# first-alert-shield.net
KiCad netlist of a schematic drawn in EAGLE
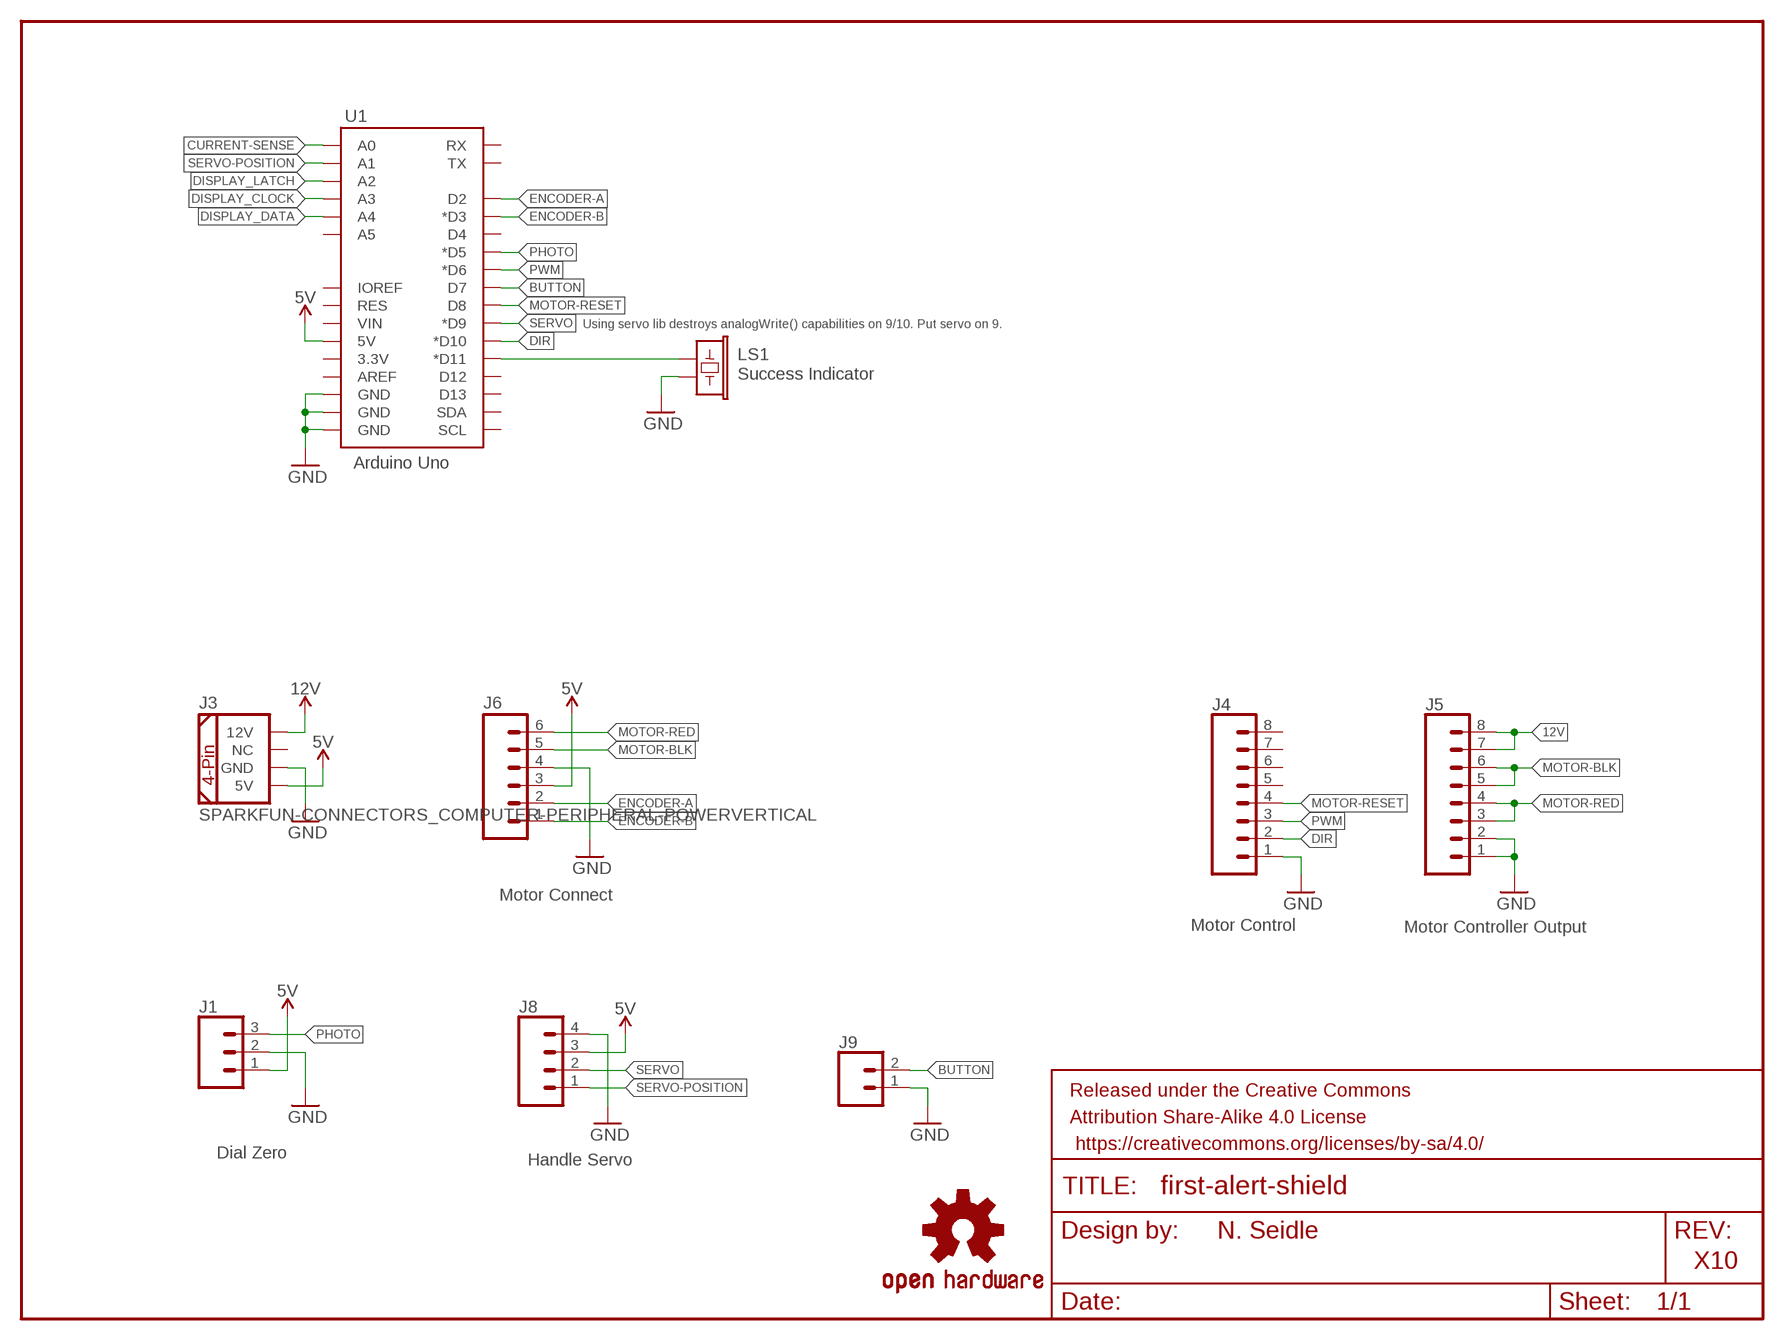
[diagram p0: schematic, sheet 1]

(export (version "E")
  (design (tool "Eeschema 10.0.6"))
  (components
    (comp (ref "FRAME1")
      (value "FRAME-LETTER")
      (footprint "eagle-import:CREATIVE_COMMONS")
      (libsource (lib "eagle-import") (part "FRAME-LETTER"))
    )
    (comp (ref "J1")
      (value "CONN_03JST-PTH-VERT")
      (footprint "eagle-import:JST-3-PTH-VERT")
      (libsource (lib "eagle-import") (part "CONN_03JST-PTH-VERT"))
    )
    (comp (ref "J3")
      (value "SPARKFUN-CONNECTORS_COMPUTER-PERIPHERAL-POWERVERTICAL")
      (footprint "eagle-import:SPARKFUN-CONNECTORS_COMPUTER-PERIPHERAL-POWER")
      (libsource (lib "eagle-import") (part "SPARKFUN-CONNECTORS_COMPUTER-PERIPHERAL-POWERVERTICAL"))
    )
    (comp (ref "J4")
      (value "Motor Control")
      (footprint "eagle-import:1X08")
      (libsource (lib "eagle-import") (part "CONN_08{dblquote}"))
    )
    (comp (ref "J5")
      (value "Motor Controller Output")
      (footprint "eagle-import:1X08")
      (libsource (lib "eagle-import") (part "CONN_08{dblquote}"))
    )
    (comp (ref "J6")
      (value "Motor Connect")
      (footprint "eagle-import:1X06@1")
      (libsource (lib "eagle-import") (part "M06SILK_FEMALE_PTH"))
    )
    (comp (ref "J8")
      (value "Handle Servo")
      (footprint "eagle-import:1X04")
      (libsource (lib "eagle-import") (part "CONN_04"))
    )
    (comp (ref "J9")
      (value "CONN_02JST-PTH-VERT")
      (footprint "eagle-import:JST-2-PTH-VERT")
      (libsource (lib "eagle-import") (part "CONN_02JST-PTH-VERT"))
    )
    (comp (ref "LOGO2")
      (value "OSHW-LOGOS")
      (footprint "eagle-import:OSHW-LOGO-S")
      (libsource (lib "eagle-import") (part "OSHW-LOGOS"))
    )
    (comp (ref "LS1")
      (value "Success Indicator")
      (footprint "eagle-import:BUZZER-12MM")
      (libsource (lib "eagle-import") (part "BUZZER-PTH"))
    )
    (comp (ref "U1")
      (value "Arduino Uno")
      (footprint "eagle-import:UNO_R3_SHIELD_NOLABELS")
      (libsource (lib "eagle-import") (part "ARDUINO_R3_SHIELDNOLABELS"))
    )
  )
  (nets
    (net (code "1") (name "5V") (class "Default")
      (node (ref "J1") (pin "1") (pinfunction "1_1") (pintype "passive"))
      (node (ref "J3") (pin "5V") (pinfunction "5V_5V") (pintype "passive"))
      (node (ref "J6") (pin "3") (pinfunction "3_3") (pintype "passive"))
      (node (ref "J8") (pin "3") (pinfunction "3_3") (pintype "passive"))
      (node (ref "U1") (pin "5V") (pinfunction "5V_5V") (pintype "bidirectional"))
    )
    (net (code "2") (name "12V") (class "Default")
      (node (ref "J3") (pin "12V") (pinfunction "12V_12V") (pintype "passive"))
      (node (ref "J5") (pin "7") (pinfunction "7_7") (pintype "passive"))
      (node (ref "J5") (pin "8") (pinfunction "8_8") (pintype "passive"))
    )
    (net (code "3") (name "BUTTON") (class "Default")
      (node (ref "J9") (pin "2") (pinfunction "2_2") (pintype "passive"))
      (node (ref "U1") (pin "D7") (pinfunction "D7_D7") (pintype "bidirectional"))
    )
    (net (code "4") (name "CURRENT-SENSE") (class "Default")
      (node (ref "U1") (pin "A0") (pinfunction "A0_A0") (pintype "bidirectional"))
    )
    (net (code "5") (name "DIR") (class "Default")
      (node (ref "J4") (pin "2") (pinfunction "2_2") (pintype "passive"))
      (node (ref "U1") (pin "D10") (pinfunction "*D10_D10") (pintype "bidirectional"))
    )
    (net (code "6") (name "DISPLAY_CLOCK") (class "Default")
      (node (ref "U1") (pin "A3") (pinfunction "A3_A3") (pintype "bidirectional"))
    )
    (net (code "7") (name "DISPLAY_DATA") (class "Default")
      (node (ref "U1") (pin "A4") (pinfunction "A4_A4") (pintype "bidirectional"))
    )
    (net (code "8") (name "DISPLAY_LATCH") (class "Default")
      (node (ref "U1") (pin "A2") (pinfunction "A2_A2") (pintype "bidirectional"))
    )
    (net (code "9") (name "ENCODER-A") (class "Default")
      (node (ref "J6") (pin "2") (pinfunction "2_2") (pintype "passive"))
      (node (ref "U1") (pin "D2") (pinfunction "D2_D2") (pintype "bidirectional"))
    )
    (net (code "10") (name "ENCODER-B") (class "Default")
      (node (ref "J6") (pin "1") (pinfunction "1_1") (pintype "passive"))
      (node (ref "U1") (pin "D3") (pinfunction "*D3_D3") (pintype "bidirectional"))
    )
    (net (code "11") (name "GND") (class "Default")
      (node (ref "J1") (pin "2") (pinfunction "2_2") (pintype "passive"))
      (node (ref "J3") (pin "GND") (pinfunction "GND_GND") (pintype "passive"))
      (node (ref "J4") (pin "1") (pinfunction "1_1") (pintype "passive"))
      (node (ref "J5") (pin "1") (pinfunction "1_1") (pintype "passive"))
      (node (ref "J5") (pin "2") (pinfunction "2_2") (pintype "passive"))
      (node (ref "J6") (pin "4") (pinfunction "4_4") (pintype "passive"))
      (node (ref "J8") (pin "4") (pinfunction "4_4") (pintype "passive"))
      (node (ref "J9") (pin "1") (pinfunction "1_1") (pintype "passive"))
      (node (ref "LS1") (pin "-") (pinfunction "2_-") (pintype "passive"))
      (node (ref "U1") (pin "GND@0") (pinfunction "GND_GND@0") (pintype "bidirectional"))
      (node (ref "U1") (pin "GND@1") (pinfunction "GND_GND@1") (pintype "bidirectional"))
      (node (ref "U1") (pin "GND@2") (pinfunction "GND_GND@2") (pintype "bidirectional"))
    )
    (net (code "12") (name "MOTOR-BLK") (class "Default")
      (node (ref "J5") (pin "5") (pinfunction "5_5") (pintype "passive"))
      (node (ref "J5") (pin "6") (pinfunction "6_6") (pintype "passive"))
      (node (ref "J6") (pin "5") (pinfunction "5_5") (pintype "passive"))
    )
    (net (code "13") (name "MOTOR-RED") (class "Default")
      (node (ref "J5") (pin "3") (pinfunction "3_3") (pintype "passive"))
      (node (ref "J5") (pin "4") (pinfunction "4_4") (pintype "passive"))
      (node (ref "J6") (pin "6") (pinfunction "6_6") (pintype "passive"))
    )
    (net (code "14") (name "MOTOR-RESET") (class "Default")
      (node (ref "J4") (pin "4") (pinfunction "4_4") (pintype "passive"))
      (node (ref "U1") (pin "D8") (pinfunction "D8_D8") (pintype "bidirectional"))
    )
    (net (code "15") (name "Net-(LS1-1)") (class "Default")
      (node (ref "LS1") (pin "+") (pinfunction "1_+") (pintype "passive"))
      (node (ref "U1") (pin "D11") (pinfunction "*D11_D11") (pintype "bidirectional"))
    )
    (net (code "16") (name "PHOTO") (class "Default")
      (node (ref "J1") (pin "3") (pinfunction "3_3") (pintype "passive"))
      (node (ref "U1") (pin "D5") (pinfunction "*D5_D5") (pintype "bidirectional"))
    )
    (net (code "17") (name "PWM") (class "Default")
      (node (ref "J4") (pin "3") (pinfunction "3_3") (pintype "passive"))
      (node (ref "U1") (pin "D6") (pinfunction "*D6_D6") (pintype "bidirectional"))
    )
    (net (code "18") (name "SERVO") (class "Default")
      (node (ref "J8") (pin "2") (pinfunction "2_2") (pintype "passive"))
      (node (ref "U1") (pin "D9") (pinfunction "*D9_D9") (pintype "bidirectional"))
    )
    (net (code "19") (name "SERVO-POSITION") (class "Default")
      (node (ref "J8") (pin "1") (pinfunction "1_1") (pintype "passive"))
      (node (ref "U1") (pin "A1") (pinfunction "A1_A1") (pintype "bidirectional"))
    )
    (net (code "20") (name "unconnected-(J3-PadNC)") (class "Default")
      (node (ref "J3") (pin "NC") (pinfunction "NC_NC") (pintype "passive"))
    )
    (net (code "21") (name "unconnected-(J4-Pad5)") (class "Default")
      (node (ref "J4") (pin "5") (pinfunction "5_5") (pintype "passive"))
    )
    (net (code "22") (name "unconnected-(J4-Pad6)") (class "Default")
      (node (ref "J4") (pin "6") (pinfunction "6_6") (pintype "passive"))
    )
    (net (code "23") (name "unconnected-(J4-Pad7)") (class "Default")
      (node (ref "J4") (pin "7") (pinfunction "7_7") (pintype "passive"))
    )
    (net (code "24") (name "unconnected-(J4-Pad8)") (class "Default")
      (node (ref "J4") (pin "8") (pinfunction "8_8") (pintype "passive"))
    )
    (net (code "25") (name "unconnected-(U1-Pad3.3V)") (class "Default")
      (node (ref "U1") (pin "3.3V") (pinfunction "3.3V_3.3V") (pintype "bidirectional"))
    )
    (net (code "26") (name "unconnected-(U1-PadA5)") (class "Default")
      (node (ref "U1") (pin "A5") (pinfunction "A5_A5") (pintype "bidirectional"))
    )
    (net (code "27") (name "unconnected-(U1-PadAREF)") (class "Default")
      (node (ref "U1") (pin "AREF") (pinfunction "AREF_AREF") (pintype "bidirectional"))
    )
    (net (code "28") (name "unconnected-(U1-PadD4)") (class "Default")
      (node (ref "U1") (pin "D4") (pinfunction "D4_D4") (pintype "bidirectional"))
    )
    (net (code "29") (name "unconnected-(U1-PadD12)") (class "Default")
      (node (ref "U1") (pin "D12") (pinfunction "D12_D12") (pintype "bidirectional"))
    )
    (net (code "30") (name "unconnected-(U1-PadD13)") (class "Default")
      (node (ref "U1") (pin "D13") (pinfunction "D13_D13") (pintype "bidirectional"))
    )
    (net (code "31") (name "unconnected-(U1-PadIOREF)") (class "Default")
      (node (ref "U1") (pin "IOREF") (pinfunction "IOREF_IOREF") (pintype "bidirectional"))
    )
    (net (code "32") (name "unconnected-(U1-PadRES)") (class "Default")
      (node (ref "U1") (pin "RES") (pinfunction "RES_RES") (pintype "bidirectional"))
    )
    (net (code "33") (name "unconnected-(U1-PadRX)") (class "Default")
      (node (ref "U1") (pin "RX") (pinfunction "RX_RX") (pintype "bidirectional"))
    )
    (net (code "34") (name "unconnected-(U1-PadSCL)") (class "Default")
      (node (ref "U1") (pin "SCL") (pinfunction "SCL_SCL") (pintype "bidirectional"))
    )
    (net (code "35") (name "unconnected-(U1-PadSDA)") (class "Default")
      (node (ref "U1") (pin "SDA") (pinfunction "SDA_SDA") (pintype "bidirectional"))
    )
    (net (code "36") (name "unconnected-(U1-PadTX)") (class "Default")
      (node (ref "U1") (pin "TX") (pinfunction "TX_TX") (pintype "bidirectional"))
    )
    (net (code "37") (name "unconnected-(U1-PadVIN)") (class "Default")
      (node (ref "U1") (pin "VIN") (pinfunction "VIN_VIN") (pintype "bidirectional"))
    )
  )
)
